# 8_-GSM_MODEM_CONNECTORS.net
KiCad netlist of a schematic drawn in Altium Designer
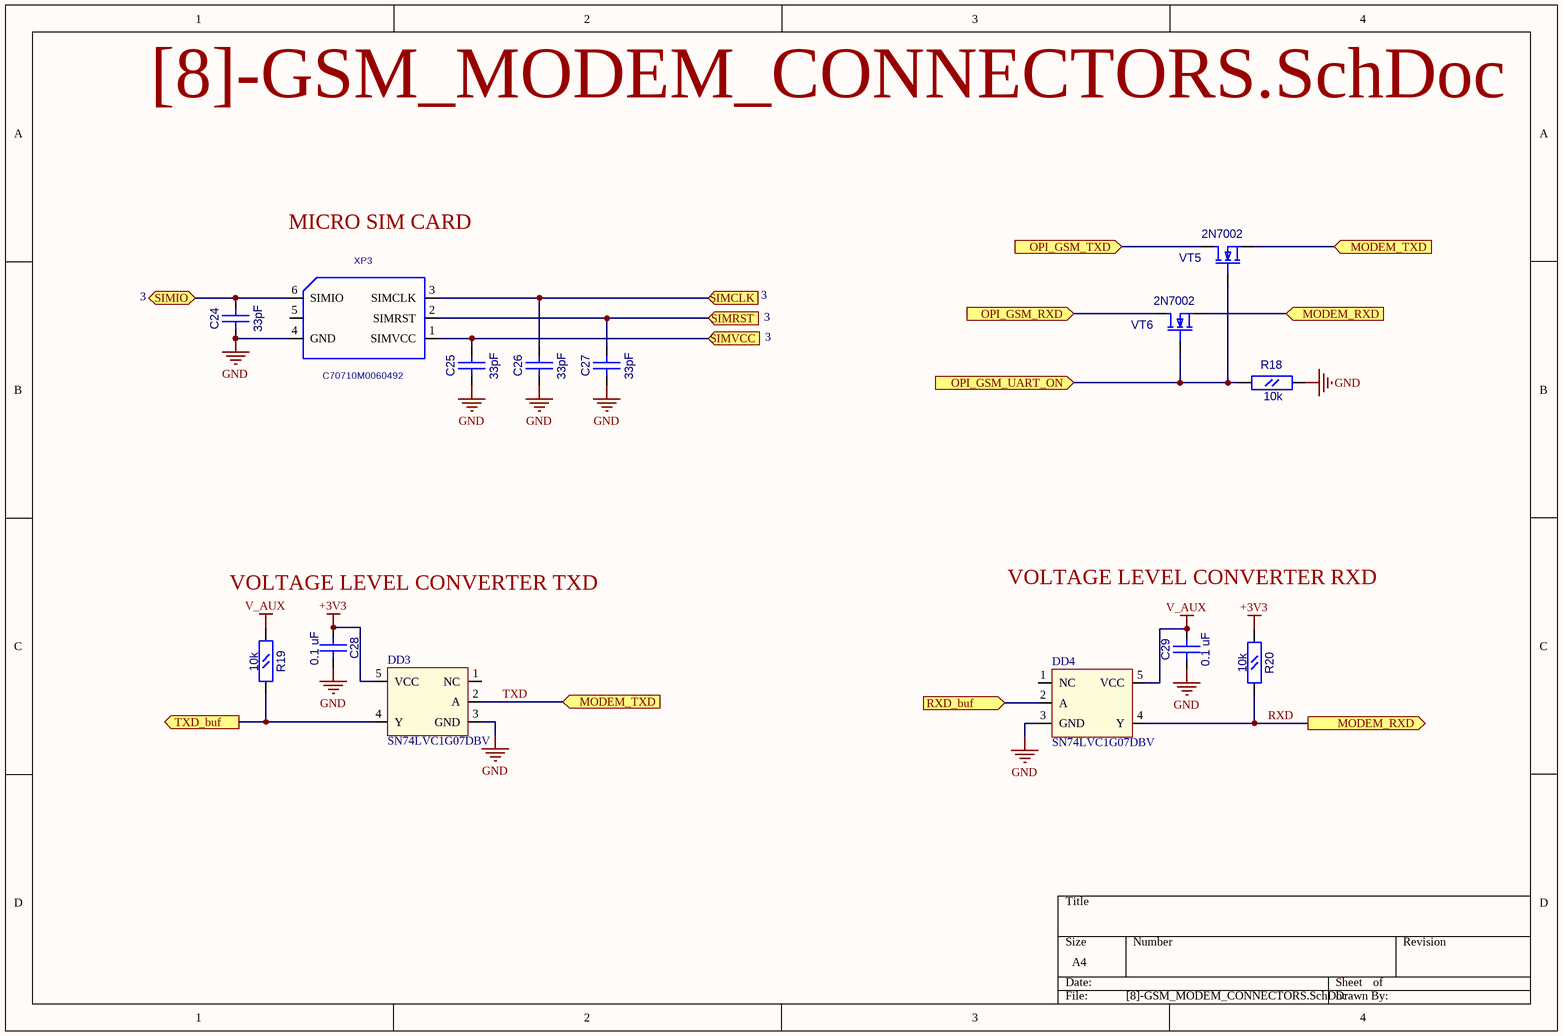
[diagram p0: [8]-GSM_MODEM_CONNECTORS.SchDoc]

(export (version "E")
  (design (tool "Eeschema 10.0.6"))
  (components
    (comp (ref "C24")
      (value "33pF")
      (footprint "CC0603")
      (description "CC0603")
      (libsource (lib "gprs_modem_2") (part "CC0603"))
    )
    (comp (ref "C25")
      (value "33pF")
      (footprint "CC0603")
      (description "CC0603")
      (libsource (lib "gprs_modem_2") (part "CC0603"))
    )
    (comp (ref "C26")
      (value "33pF")
      (footprint "CC0603")
      (description "CC0603")
      (libsource (lib "gprs_modem_2") (part "CC0603"))
    )
    (comp (ref "C27")
      (value "33pF")
      (footprint "CC0603")
      (description "CC0603")
      (libsource (lib "gprs_modem_2") (part "CC0603"))
    )
    (comp (ref "C28")
      (value "0.1 uF")
      (footprint "CC0603")
      (description "CC0603")
      (libsource (lib "gprs_modem_2") (part "CC0603"))
    )
    (comp (ref "C29")
      (value "0.1 uF")
      (footprint "CC0603")
      (description "CC0603")
      (libsource (lib "gprs_modem_2") (part "CC0603"))
    )
    (comp (ref "DD3")
      (value "SN74LVC1G07DBV")
      (footprint "SOT23-5")
      (description "Open Drain Single Bus Bufer")
      (libsource (lib "gprs_modem_2") (part "SN74LVC1G07DBV"))
    )
    (comp (ref "DD4")
      (value "SN74LVC1G07DBV")
      (footprint "SOT23-5")
      (description "Open Drain Single Bus Bufer")
      (libsource (lib "") (part "SN74LVC1G07DBV_1"))
    )
    (comp (ref "R18")
      (value "10k")
      (footprint "RC0603")
      (description "RC0603")
      (libsource (lib "fizik_lib") (part "RC0603"))
    )
    (comp (ref "R19")
      (value "10k")
      (footprint "RC0603")
      (description "RC0603")
      (libsource (lib "gprs_modem_2") (part "RC0603"))
    )
    (comp (ref "R20")
      (value "10k")
      (footprint "RC0603")
      (description "RC0603")
      (libsource (lib "gprs_modem_2") (part "RC0603"))
    )
    (comp (ref "VT5")
      (value "2N7002")
      (footprint "SOT-23(123)")
      (description "N-Channel Enhancement Mode Vertical DMOS FET")
      (libsource (lib "fizik_lib") (part "2N7002"))
    )
    (comp (ref "VT6")
      (value "2N7002")
      (footprint "SOT-23(123)")
      (description "N-Channel Enhancement Mode Vertical DMOS FET")
      (libsource (lib "fizik_lib") (part "2N7002"))
    )
    (comp (ref "XP3")
      (value "C70710M0060492")
      (footprint "SCVW06A25020")
      (description "SCV-W06A25-020")
      (libsource (lib "gprs_modem_2") (part "SCV-W06A25-020"))
    )
  )
  (nets
    (net (code "1") (name "+3V3") (class "Default")
      (node (ref "C28") (pin "2") (pinfunction "B_2") (pintype "passive"))
      (node (ref "DD3") (pin "5") (pinfunction "VCC_5") (pintype "passive"))
      (node (ref "R20") (pin "1") (pinfunction "A_1") (pintype "passive"))
    )
    (net (code "2") (name "/OPI_GSM_RXD") (class "Default")
      (node (ref "VT6") (pin "3") (pinfunction "D_3") (pintype "passive"))
    )
    (net (code "3") (name "/OPI_GSM_TXD") (class "Default")
      (node (ref "VT5") (pin "3") (pinfunction "D_3") (pintype "passive"))
    )
    (net (code "4") (name "/OPI_GSM_UART_ON") (class "Default")
      (node (ref "R18") (pin "1") (pinfunction "A_1") (pintype "passive"))
      (node (ref "VT5") (pin "1") (pinfunction "G_1") (pintype "passive"))
      (node (ref "VT6") (pin "1") (pinfunction "G_1") (pintype "passive"))
    )
    (net (code "5") (name "/RXD") (class "Default")
      (node (ref "DD4") (pin "4") (pinfunction "Y_4") (pintype "passive"))
      (node (ref "R20") (pin "2") (pinfunction "B_2") (pintype "passive"))
      (node (ref "VT6") (pin "2") (pinfunction "S_2") (pintype "passive"))
    )
    (net (code "6") (name "/RXD_buf") (class "Default")
      (node (ref "DD4") (pin "2") (pinfunction "A_2") (pintype "passive"))
    )
    (net (code "7") (name "/SIMCLK") (class "Default")
      (node (ref "C26") (pin "2") (pinfunction "B_2") (pintype "passive"))
      (node (ref "XP3") (pin "3") (pinfunction "SIMCLK_3") (pintype "passive"))
    )
    (net (code "8") (name "/SIMIO") (class "Default")
      (node (ref "C24") (pin "2") (pinfunction "B_2") (pintype "passive"))
      (node (ref "XP3") (pin "6") (pinfunction "SIMIO_6") (pintype "passive"))
    )
    (net (code "9") (name "/SIMRST") (class "Default")
      (node (ref "C27") (pin "2") (pinfunction "B_2") (pintype "passive"))
      (node (ref "XP3") (pin "2") (pinfunction "SIMRST_2") (pintype "passive"))
    )
    (net (code "10") (name "/SIMVCC") (class "Default")
      (node (ref "C25") (pin "2") (pinfunction "B_2") (pintype "passive"))
      (node (ref "XP3") (pin "1") (pinfunction "SIMVCC_1") (pintype "passive"))
    )
    (net (code "11") (name "/TXD") (class "Default")
      (node (ref "DD3") (pin "2") (pinfunction "A_2") (pintype "passive"))
      (node (ref "VT5") (pin "2") (pinfunction "S_2") (pintype "passive"))
    )
    (net (code "12") (name "/TXD_buf") (class "Default")
      (node (ref "DD3") (pin "4") (pinfunction "Y_4") (pintype "passive"))
      (node (ref "R19") (pin "2") (pinfunction "B_2") (pintype "passive"))
    )
    (net (code "13") (name "GND") (class "Default")
      (node (ref "C24") (pin "1") (pinfunction "A_1") (pintype "passive"))
      (node (ref "C25") (pin "1") (pinfunction "A_1") (pintype "passive"))
      (node (ref "C26") (pin "1") (pinfunction "A_1") (pintype "passive"))
      (node (ref "C27") (pin "1") (pinfunction "A_1") (pintype "passive"))
      (node (ref "C28") (pin "1") (pinfunction "A_1") (pintype "passive"))
      (node (ref "C29") (pin "1") (pinfunction "A_1") (pintype "passive"))
      (node (ref "DD3") (pin "3") (pinfunction "GND_3") (pintype "passive"))
      (node (ref "DD4") (pin "3") (pinfunction "GND_3") (pintype "passive"))
      (node (ref "R18") (pin "2") (pinfunction "B_2") (pintype "passive"))
      (node (ref "XP3") (pin "4") (pinfunction "GND_4") (pintype "passive"))
    )
    (net (code "14") (name "V_AUX") (class "Default")
      (node (ref "C29") (pin "2") (pinfunction "B_2") (pintype "passive"))
      (node (ref "DD4") (pin "5") (pinfunction "VCC_5") (pintype "passive"))
      (node (ref "R19") (pin "1") (pinfunction "A_1") (pintype "passive"))
    )
    (net (code "15") (name "unconnected-(DD3-NC-Pad1)") (class "Default")
      (node (ref "DD3") (pin "1") (pinfunction "NC_1") (pintype "passive"))
    )
    (net (code "16") (name "unconnected-(DD4-NC-Pad1)") (class "Default")
      (node (ref "DD4") (pin "1") (pinfunction "NC_1") (pintype "passive"))
    )
    (net (code "17") (name "unconnected-(XP3-Pad5)") (class "Default")
      (node (ref "XP3") (pin "5") (pintype "passive"))
    )
  )
)
